# design.net
KiCad netlist of a schematic drawn in Altium Designer
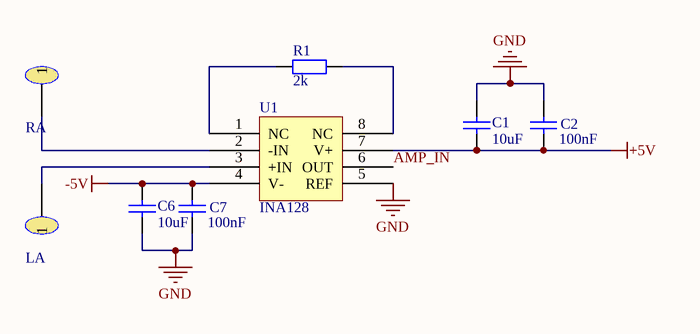
[diagram p0: 前级仪表放大.SchDoc]

(export (version "E")
  (design (tool "Eeschema 10.0.6"))
  (components
    (comp (ref "C1")
      (value "10uF")
      (footprint "LC-0805_C")
      (description "100nF��0805��50V,+/-10%")
      (libsource (lib "ECG") (part "Cap"))
    )
    (comp (ref "C2")
      (value "100nF")
      (footprint "LC-0805_C")
      (description "100nF��0805��50V,+/-10%")
      (libsource (lib "ECG") (part "Cap"))
    )
    (comp (ref "C6")
      (value "10uF")
      (footprint "LC-0805_C")
      (description "100nF��0805��50V,+/-10%")
      (libsource (lib "ECG") (part "Cap"))
    )
    (comp (ref "C7")
      (value "100nF")
      (footprint "LC-0805_C")
      (description "100nF��0805��50V,+/-10%")
      (libsource (lib "ECG") (part "Cap"))
    )
    (comp (ref "LA")
      (value "���Ժ���")
      (footprint "PAD")
      (description "��������")
      (libsource (lib "ECG") (part "TestPoint"))
    )
    (comp (ref "R1")
      (value "2k")
      (footprint "LC-0805_R")
      (description "330��,0805,��5%")
      (libsource (lib "ECG") (part "Res1"))
    )
    (comp (ref "RA")
      (value "���Ժ���")
      (footprint "PAD")
      (description "��������")
      (libsource (lib "ECG") (part "TestPoint"))
    )
    (comp (ref "U1")
      (value "INA128")
      (footprint "LC-SOIC-8_150mil")
      (description "INA128��SO-8")
      (libsource (lib "ECG") (part "INA128"))
    )
  )
  (nets
    (net (code "1") (name "+5V") (class "Default")
      (node (ref "C1") (pin "2") (pinfunction "2_2") (pintype "passive"))
      (node (ref "C2") (pin "2") (pinfunction "2_2") (pintype "passive"))
      (node (ref "U1") (pin "7") (pinfunction "V+_7") (pintype "passive"))
    )
    (net (code "2") (name "-5V") (class "Default")
      (node (ref "C6") (pin "1") (pinfunction "1_1") (pintype "passive"))
      (node (ref "C7") (pin "1") (pinfunction "1_1") (pintype "passive"))
      (node (ref "U1") (pin "4") (pinfunction "V-_4") (pintype "passive"))
    )
    (net (code "3") (name "/AMP_IN") (class "Default")
      (node (ref "U1") (pin "6") (pinfunction "OUT_6") (pintype "passive"))
    )
    (net (code "4") (name "GND") (class "Default")
      (node (ref "C1") (pin "1") (pinfunction "1_1") (pintype "passive"))
      (node (ref "C2") (pin "1") (pinfunction "1_1") (pintype "passive"))
      (node (ref "C6") (pin "2") (pinfunction "2_2") (pintype "passive"))
      (node (ref "C7") (pin "2") (pinfunction "2_2") (pintype "passive"))
      (node (ref "U1") (pin "5") (pinfunction "REF_5") (pintype "passive"))
    )
    (net (code "5") (name "Net-(R1-Pad1)") (class "Default")
      (node (ref "R1") (pin "1") (pinfunction "1_1") (pintype "passive"))
      (node (ref "U1") (pin "1") (pinfunction "NC_1") (pintype "passive"))
    )
    (net (code "6") (name "Net-(R1-Pad2)") (class "Default")
      (node (ref "R1") (pin "2") (pinfunction "2_2") (pintype "passive"))
      (node (ref "U1") (pin "8") (pinfunction "NC_8") (pintype "passive"))
    )
    (net (code "7") (name "Net-(U1-+IN)") (class "Default")
      (node (ref "LA") (pin "1") (pinfunction "1_1") (pintype "passive"))
      (node (ref "U1") (pin "3") (pinfunction "+IN_3") (pintype "passive"))
    )
    (net (code "8") (name "Net-(U1--IN)") (class "Default")
      (node (ref "RA") (pin "1") (pinfunction "1_1") (pintype "passive"))
      (node (ref "U1") (pin "2") (pinfunction "-IN_2") (pintype "passive"))
    )
  )
)
